# lm4811.net
KiCad netlist of a schematic drawn in EAGLE
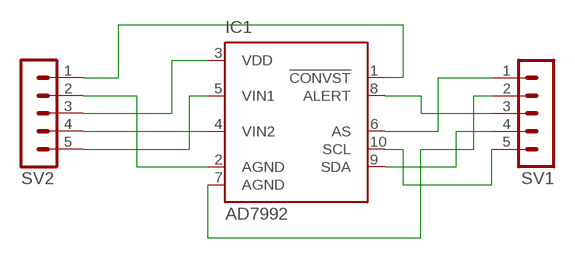
[diagram p0: schematic, sheet 1]

(export (version "E")
  (design (tool "Eeschema 10.0.6"))
  (components
    (comp (ref "IC1")
      (value "AD7992")
      (footprint "eagle-import:MSOP10")
      (fields (field (name "MPN") "AD7992BRMZ-0"))
      (libsource (lib "eagle-import") (part "AD7992"))
    )
    (comp (ref "SV1")
      (value "MA05-1")
      (footprint "eagle-import:MA05-1")
      (libsource (lib "eagle-import") (part "MA05-1"))
    )
    (comp (ref "SV2")
      (value "MA05-1")
      (footprint "eagle-import:MA05-1")
      (libsource (lib "eagle-import") (part "MA05-1"))
    )
  )
  (nets
    (net (code "1") (name "Net-(IC1-AGND-Pad2)") (class "Default")
      (node (ref "IC1") (pin "2") (pinfunction "AGND_2") (pintype "power_in"))
      (node (ref "SV2") (pin "2") (pinfunction "2_2") (pintype "passive"))
    )
    (net (code "2") (name "Net-(IC1-AGND-Pad7)") (class "Default")
      (node (ref "IC1") (pin "7") (pinfunction "AGND_7") (pintype "power_in"))
      (node (ref "SV1") (pin "2") (pinfunction "2_2") (pintype "passive"))
    )
    (net (code "3") (name "Net-(IC1-ALERT)") (class "Default")
      (node (ref "IC1") (pin "8") (pinfunction "ALERT_8") (pintype "output"))
      (node (ref "SV1") (pin "3") (pinfunction "3_3") (pintype "passive"))
    )
    (net (code "4") (name "Net-(IC1-AS)") (class "Default")
      (node (ref "IC1") (pin "6") (pinfunction "AS_6") (pintype "input"))
      (node (ref "SV1") (pin "1") (pinfunction "1_1") (pintype "passive"))
    )
    (net (code "5") (name "Net-(IC1-SCL)") (class "Default")
      (node (ref "IC1") (pin "10") (pinfunction "SCL_10") (pintype "input"))
      (node (ref "SV1") (pin "5") (pinfunction "5_5") (pintype "passive"))
    )
    (net (code "6") (name "Net-(IC1-SDA)") (class "Default")
      (node (ref "IC1") (pin "9") (pinfunction "SDA_9") (pintype "bidirectional"))
      (node (ref "SV1") (pin "4") (pinfunction "4_4") (pintype "passive"))
    )
    (net (code "7") (name "Net-(IC1-VDD)") (class "Default")
      (node (ref "IC1") (pin "3") (pinfunction "VDD_3") (pintype "power_in"))
      (node (ref "SV2") (pin "3") (pinfunction "3_3") (pintype "passive"))
    )
    (net (code "8") (name "Net-(IC1-VIN1)") (class "Default")
      (node (ref "IC1") (pin "5") (pinfunction "VIN1_5") (pintype "input"))
      (node (ref "SV2") (pin "5") (pinfunction "5_5") (pintype "passive"))
    )
    (net (code "9") (name "Net-(IC1-VIN2)") (class "Default")
      (node (ref "IC1") (pin "4") (pinfunction "VIN2_4") (pintype "input"))
      (node (ref "SV2") (pin "4") (pinfunction "4_4") (pintype "passive"))
    )
    (net (code "10") (name "Net-(IC1-~{CONVST})") (class "Default")
      (node (ref "IC1") (pin "1") (pinfunction "~{CONVST}_1") (pintype "input"))
      (node (ref "SV2") (pin "1") (pinfunction "1_1") (pintype "passive"))
    )
  )
)
